# 7_-_ADC_Chip.net
KiCad netlist of a schematic drawn in Altium Designer
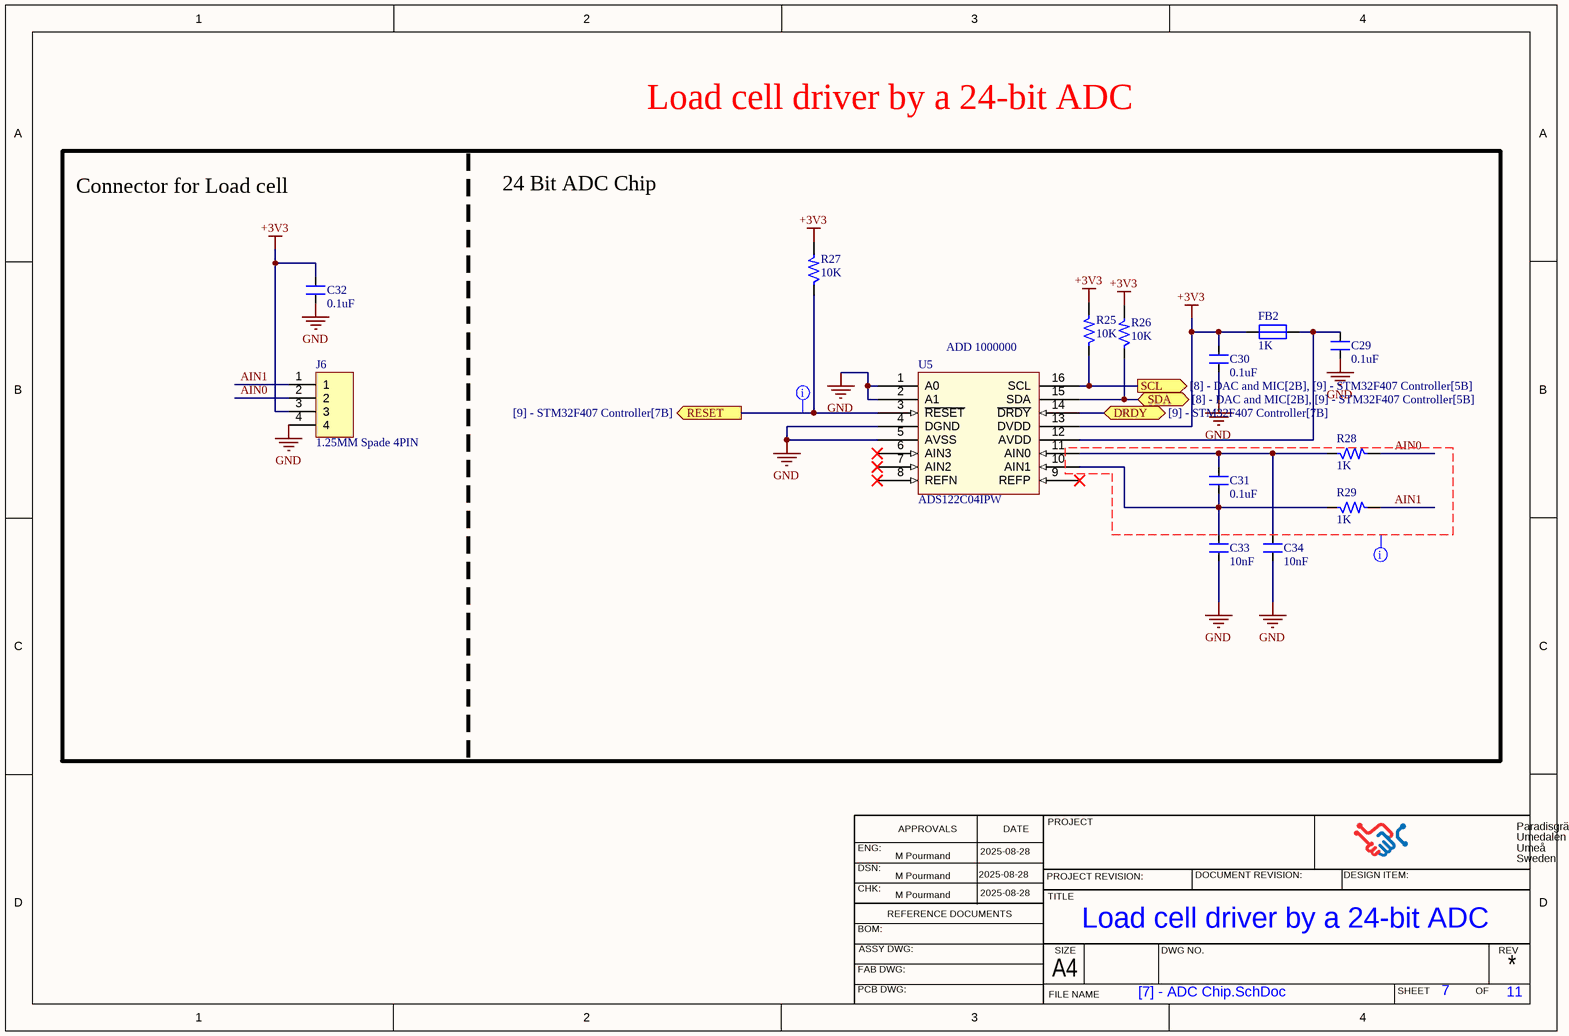
[diagram p0: [7] - ADC Chip.SchDoc]

(export (version "E")
  (design (tool "Eeschema 10.0.6"))
  (components
    (comp (ref "C29")
      (value "0.1uF")
      (footprint "CAP_0805")
      (description "0.1µF ±10% 50V Ceramic Capacitor X7R 0805 (2012 Metric)")
      (fields
        (field (name "MANUFACTURER") "Samsung")
        (field (name "MANUFACTURER PART NUMBER") "CL21B104KBCNNNC")
      )
      (libsource (lib "ESTEEMPCBLIB") (part "CAP_0.1uF-50V-10%-0805"))
    )
    (comp (ref "C30")
      (value "0.1uF")
      (footprint "CAP_0805")
      (description "0.1µF ±10% 50V Ceramic Capacitor X7R 0805 (2012 Metric)")
      (fields
        (field (name "MANUFACTURER") "Samsung")
        (field (name "MANUFACTURER PART NUMBER") "CL21B104KBCNNNC")
      )
      (libsource (lib "ESTEEMPCBLIB") (part "CAP_0.1uF-50V-10%-0805"))
    )
    (comp (ref "C31")
      (value "0.1uF")
      (footprint "CAP_0805")
      (description "0.1µF ±10% 50V Ceramic Capacitor X7R 0805 (2012 Metric)")
      (fields
        (field (name "MANUFACTURER") "Samsung")
        (field (name "MANUFACTURER PART NUMBER") "CL21B104KBCNNNC")
      )
      (libsource (lib "ESTEEMPCBLIB") (part "CAP_0.1uF-50V-10%-0805"))
    )
    (comp (ref "C32")
      (value "0.1uF")
      (footprint "CAP_0805")
      (description "0.1µF ±10% 50V Ceramic Capacitor X7R 0805 (2012 Metric)")
      (fields
        (field (name "MANUFACTURER") "Samsung")
        (field (name "MANUFACTURER PART NUMBER") "CL21B104KBCNNNC")
      )
      (libsource (lib "ESTEEMPCBLIB") (part "CAP_0.1uF-50V-10%-0805"))
    )
    (comp (ref "C33")
      (value "10nF")
      (footprint "CAP_0805")
      (description "10000pF ±10% 50V Ceramic Capacitor X7R 0805 (2012 Metric)")
      (fields
        (field (name "MANUFACTURER") "Samsung")
        (field (name "MANUFACTURER PART NUMBER") "C0805C103K5RECAUTO")
      )
      (libsource (lib "ESTEEMPCBLIB") (part "CAP_10nF-50V-10%-0805"))
    )
    (comp (ref "C34")
      (value "10nF")
      (footprint "CAP_0805")
      (description "10000pF ±10% 50V Ceramic Capacitor X7R 0805 (2012 Metric)")
      (fields
        (field (name "MANUFACTURER") "Samsung")
        (field (name "MANUFACTURER PART NUMBER") "C0805C103K5RECAUTO")
      )
      (libsource (lib "ESTEEMPCBLIB") (part "CAP_10nF-50V-10%-0805"))
    )
    (comp (ref "FB2")
      (value "1K")
      (footprint "IND_0805")
      (description "1 kOhms @ 100MHz 1 Power Line Ferrite Bead 0805 (2012 Metric) 1.6A")
      (fields
        (field (name "MANUFACTURER") "Laird")
        (field (name "MANUFACTURER PART NUMBER") "BLM21SP102SH1D")
      )
      (libsource (lib "ESTEEMPCBLIB") (part "FB_1K-100MHZ-1.6A-0805"))
    )
    (comp (ref "J6")
      (value "1.25MM Spade 4PIN")
      (footprint "CON4_50_653004117322_TH_RA")
      (description "4 Pins, 1 Row 1.25mm Pitch, right angle Connector, male")
      (fields (field (name "MANUFACTURER PART NUMBER") "653004117322") (field (name "MANUFACTURER") "JST"))
      (libsource (lib "ESTEEMPCBLIB") (part "CON-PLG_4X1-50-RA-TH"))
    )
    (comp (ref "R25")
      (value "10K")
      (footprint "RES_0603")
      (description "10 kOhms ±1% 0.1W, 1/10W Chip Resistor 0603 (1608 Metric) Automotive AEC-Q200 Thick Film")
      (fields (field (name "MANUFACTURER") "Walsin") (field (name "MANUFACTURER PART NUMBER") "WR06X1002FTL"))
      (libsource (lib "ESTEEMPCBLIB") (part "RES_10K-0.1W-1%-0603"))
    )
    (comp (ref "R26")
      (value "10K")
      (footprint "RES_0603")
      (description "10 kOhms ±1% 0.1W, 1/10W Chip Resistor 0603 (1608 Metric) Automotive AEC-Q200 Thick Film")
      (fields (field (name "MANUFACTURER") "Walsin") (field (name "MANUFACTURER PART NUMBER") "WR06X1002FTL"))
      (libsource (lib "ESTEEMPCBLIB") (part "RES_10K-0.1W-1%-0603"))
    )
    (comp (ref "R27")
      (value "10K")
      (footprint "RES_0603")
      (description "10 kOhms ±1% 0.1W, 1/10W Chip Resistor 0603 (1608 Metric) Automotive AEC-Q200 Thick Film")
      (fields (field (name "MANUFACTURER") "Walsin") (field (name "MANUFACTURER PART NUMBER") "WR06X1002FTL"))
      (libsource (lib "ESTEEMPCBLIB") (part "RES_10K-0.1W-1%-0603"))
    )
    (comp (ref "R28")
      (value "1K")
      (footprint "RES_0603")
      (description "1 kOhms ±1% 0.1W, 1/10W Chip Resistor 0603 (1608 Metric) Automotive AEC-Q200 Thick Film")
      (fields (field (name "MANUFACTURER") "Walsin") (field (name "MANUFACTURER PART NUMBER") "WR06X1001FTL"))
      (libsource (lib "ESTEEMPCBLIB") (part "RES_1K-0.1W-1%-0603"))
    )
    (comp (ref "R29")
      (value "1K")
      (footprint "RES_0603")
      (description "1 kOhms ±1% 0.1W, 1/10W Chip Resistor 0603 (1608 Metric) Automotive AEC-Q200 Thick Film")
      (fields (field (name "MANUFACTURER") "Walsin") (field (name "MANUFACTURER PART NUMBER") "WR06X1001FTL"))
      (libsource (lib "ESTEEMPCBLIB") (part "RES_1K-0.1W-1%-0603"))
    )
    (comp (ref "U5")
      (value "ADS122C04IPW")
      (footprint "TSSOP16_25-59_294_54X14_SMT")
      (description "24 Bit Analog to Digital Converter 4 Input 1 Sigma-Delta 16-TSSOP")
      (fields (field (name "MANUFACTURER") "Texas Instruments"))
      (libsource (lib "ESTEEMPCBLIB") (part "IC_ADS122C04IPW"))
    )
  )
  (nets
    (net (code "1") (name "+3V3") (class "Default")
      (node (ref "C30") (pin "2") (pinfunction "2_2") (pintype "passive"))
      (node (ref "C32") (pin "2") (pinfunction "2_2") (pintype "passive"))
      (node (ref "FB2") (pin "1") (pinfunction "1_1") (pintype "passive"))
      (node (ref "J6") (pin "3") (pinfunction "3_3") (pintype "passive"))
      (node (ref "R25") (pin "2") (pinfunction "2_2") (pintype "passive"))
      (node (ref "R26") (pin "2") (pinfunction "2_2") (pintype "passive"))
      (node (ref "R27") (pin "2") (pinfunction "2_2") (pintype "passive"))
      (node (ref "U5") (pin "13") (pinfunction "DVDD_13") (pintype "power_in"))
    )
    (net (code "2") (name "/AIN0") (class "Default")
      (node (ref "J6") (pin "2") (pinfunction "2_2") (pintype "passive"))
      (node (ref "R28") (pin "2") (pinfunction "2_2") (pintype "passive"))
    )
    (net (code "3") (name "/AIN1") (class "Default")
      (node (ref "J6") (pin "1") (pinfunction "1_1") (pintype "passive"))
      (node (ref "R29") (pin "2") (pinfunction "2_2") (pintype "passive"))
    )
    (net (code "4") (name "/DRDY") (class "Default")
      (node (ref "U5") (pin "14") (pinfunction "DRDY_14") (pintype "input"))
    )
    (net (code "5") (name "/RESET") (class "Default")
      (node (ref "R27") (pin "1") (pinfunction "1_1") (pintype "passive"))
      (node (ref "U5") (pin "3") (pinfunction "RESET_3") (pintype "input"))
    )
    (net (code "6") (name "/SCL") (class "Default")
      (node (ref "R25") (pin "1") (pinfunction "1_1") (pintype "passive"))
      (node (ref "U5") (pin "16") (pinfunction "SCL_16") (pintype "open_collector"))
    )
    (net (code "7") (name "/SDA") (class "Default")
      (node (ref "R26") (pin "1") (pinfunction "1_1") (pintype "passive"))
      (node (ref "U5") (pin "15") (pinfunction "SDA_15") (pintype "open_collector"))
    )
    (net (code "8") (name "GND") (class "Default")
      (node (ref "C29") (pin "1") (pinfunction "1_1") (pintype "passive"))
      (node (ref "C30") (pin "1") (pinfunction "1_1") (pintype "passive"))
      (node (ref "C32") (pin "1") (pinfunction "1_1") (pintype "passive"))
      (node (ref "C33") (pin "2") (pinfunction "2_2") (pintype "passive"))
      (node (ref "C34") (pin "2") (pinfunction "2_2") (pintype "passive"))
      (node (ref "J6") (pin "4") (pinfunction "4_4") (pintype "passive"))
      (node (ref "U5") (pin "1") (pinfunction "A0_1") (pintype "passive"))
      (node (ref "U5") (pin "2") (pinfunction "A1_2") (pintype "passive"))
      (node (ref "U5") (pin "4") (pinfunction "DGND_4") (pintype "power_in"))
      (node (ref "U5") (pin "5") (pinfunction "AVSS_5") (pintype "power_in"))
    )
    (net (code "9") (name "Net-(U5-AIN0)") (class "Default")
      (node (ref "C31") (pin "2") (pinfunction "2_2") (pintype "passive"))
      (node (ref "C34") (pin "1") (pinfunction "1_1") (pintype "passive"))
      (node (ref "R28") (pin "1") (pinfunction "1_1") (pintype "passive"))
      (node (ref "U5") (pin "11") (pinfunction "AIN0_11") (pintype "input"))
    )
    (net (code "10") (name "Net-(U5-AIN1)") (class "Default")
      (node (ref "C31") (pin "1") (pinfunction "1_1") (pintype "passive"))
      (node (ref "C33") (pin "1") (pinfunction "1_1") (pintype "passive"))
      (node (ref "R29") (pin "1") (pinfunction "1_1") (pintype "passive"))
      (node (ref "U5") (pin "10") (pinfunction "AIN1_10") (pintype "input"))
    )
    (net (code "11") (name "Net-(U5-AVDD)") (class "Default")
      (node (ref "C29") (pin "2") (pinfunction "2_2") (pintype "passive"))
      (node (ref "FB2") (pin "2") (pinfunction "2_2") (pintype "passive"))
      (node (ref "U5") (pin "12") (pinfunction "AVDD_12") (pintype "power_in"))
    )
    (net (code "12") (name "unconnected-(U5-AIN2-Pad7)") (class "Default")
      (node (ref "U5") (pin "7") (pinfunction "AIN2_7") (pintype "input+no_connect"))
    )
    (net (code "13") (name "unconnected-(U5-AIN3-Pad6)") (class "Default")
      (node (ref "U5") (pin "6") (pinfunction "AIN3_6") (pintype "input+no_connect"))
    )
    (net (code "14") (name "unconnected-(U5-REFN-Pad8)") (class "Default")
      (node (ref "U5") (pin "8") (pinfunction "REFN_8") (pintype "input+no_connect"))
    )
    (net (code "15") (name "unconnected-(U5-REFP-Pad9)") (class "Default")
      (node (ref "U5") (pin "9") (pinfunction "REFP_9") (pintype "input+no_connect"))
    )
  )
)
